# BusinessCard_LA_8CH.net
KiCad netlist of a schematic drawn in EAGLE
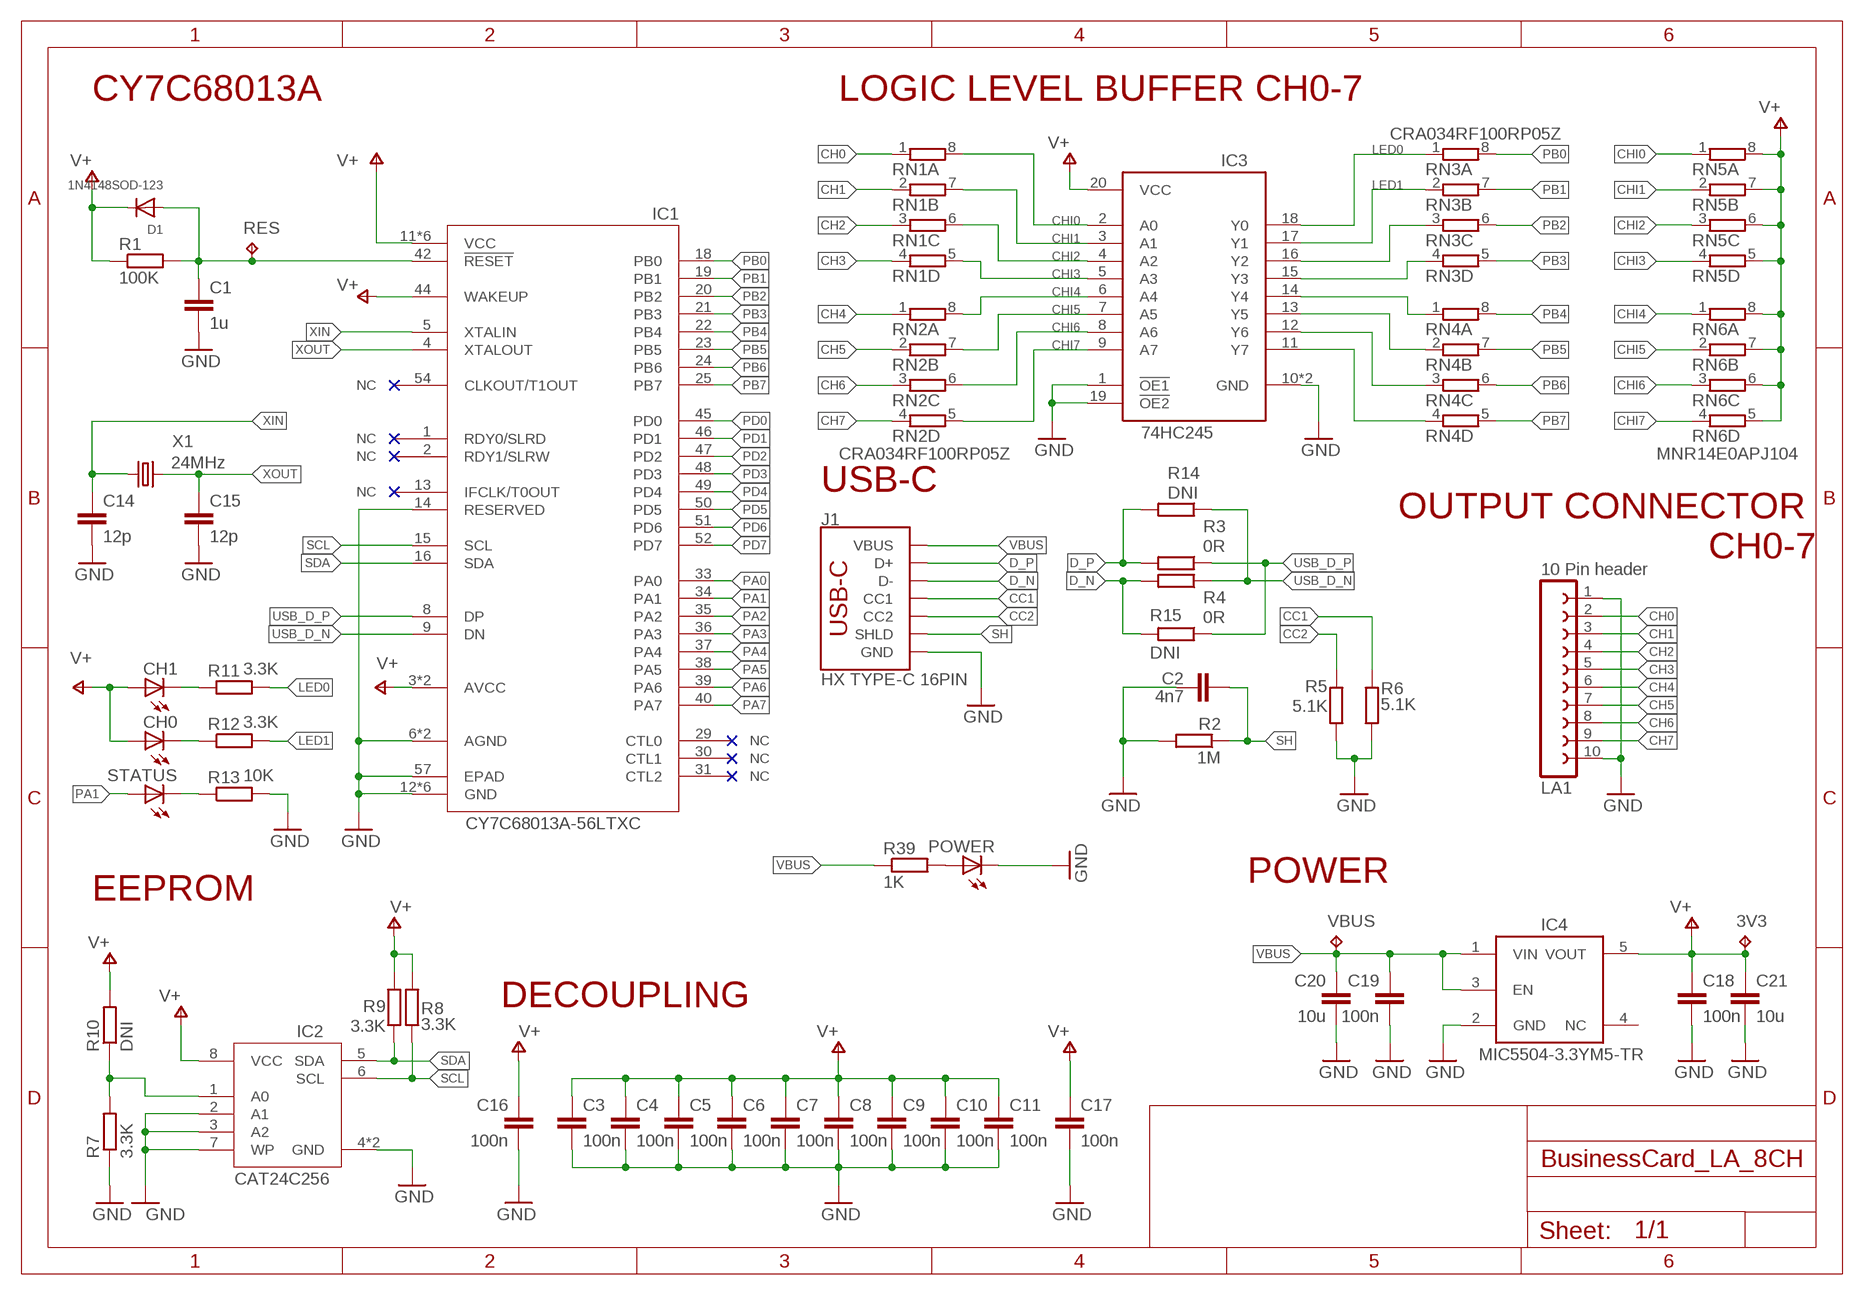
[diagram p0: schematic, sheet 1]

(export (version "E")
  (design (tool "Eeschema 10.0.6"))
  (components
    (comp (ref "3V3")
      (value "TPB1,27")
      (footprint "eagle-import:B1,27")
      (libsource (lib "eagle-import") (part "TPB1,27"))
    )
    (comp (ref "C1")
      (value "1u")
      (footprint "eagle-import:C0402K")
      (libsource (lib "eagle-import") (part "C-EUC0402K"))
    )
    (comp (ref "C2")
      (value "4n7")
      (footprint "eagle-import:C0402K")
      (libsource (lib "eagle-import") (part "C-EUC0402K"))
    )
    (comp (ref "C3")
      (value "100n")
      (footprint "eagle-import:C0402K")
      (libsource (lib "eagle-import") (part "C-EUC0402K"))
    )
    (comp (ref "C4")
      (value "100n")
      (footprint "eagle-import:C0402K")
      (libsource (lib "eagle-import") (part "C-EUC0402K"))
    )
    (comp (ref "C5")
      (value "100n")
      (footprint "eagle-import:C0402K")
      (libsource (lib "eagle-import") (part "C-EUC0402K"))
    )
    (comp (ref "C6")
      (value "100n")
      (footprint "eagle-import:C0402K")
      (libsource (lib "eagle-import") (part "C-EUC0402K"))
    )
    (comp (ref "C7")
      (value "100n")
      (footprint "eagle-import:C0402K")
      (libsource (lib "eagle-import") (part "C-EUC0402K"))
    )
    (comp (ref "C8")
      (value "100n")
      (footprint "eagle-import:C0402K")
      (libsource (lib "eagle-import") (part "C-EUC0402K"))
    )
    (comp (ref "C9")
      (value "100n")
      (footprint "eagle-import:C0402K")
      (libsource (lib "eagle-import") (part "C-EUC0402K"))
    )
    (comp (ref "C10")
      (value "100n")
      (footprint "eagle-import:C0402K")
      (libsource (lib "eagle-import") (part "C-EUC0402K"))
    )
    (comp (ref "C11")
      (value "100n")
      (footprint "eagle-import:C0402K")
      (libsource (lib "eagle-import") (part "C-EUC0402K"))
    )
    (comp (ref "C14")
      (value "12p")
      (footprint "eagle-import:C0402K")
      (libsource (lib "eagle-import") (part "C-EUC0402K"))
    )
    (comp (ref "C15")
      (value "12p")
      (footprint "eagle-import:C0402K")
      (libsource (lib "eagle-import") (part "C-EUC0402K"))
    )
    (comp (ref "C16")
      (value "100n")
      (footprint "eagle-import:C0402K")
      (libsource (lib "eagle-import") (part "C-EUC0402K"))
    )
    (comp (ref "C17")
      (value "100n")
      (footprint "eagle-import:C0402K")
      (libsource (lib "eagle-import") (part "C-EUC0402K"))
    )
    (comp (ref "C18")
      (value "100n")
      (footprint "eagle-import:C0402K")
      (libsource (lib "eagle-import") (part "C-EUC0402K"))
    )
    (comp (ref "C19")
      (value "100n")
      (footprint "eagle-import:C0402K")
      (libsource (lib "eagle-import") (part "C-EUC0402K"))
    )
    (comp (ref "C20")
      (value "10u")
      (footprint "eagle-import:C0805K")
      (libsource (lib "eagle-import") (part "C-EUC0805K"))
    )
    (comp (ref "C21")
      (value "10u")
      (footprint "eagle-import:C0805K")
      (libsource (lib "eagle-import") (part "C-EUC0805K"))
    )
    (comp (ref "CH0")
      (value "19-217/GHC-YR1S2/3T")
      (footprint "eagle-import:CHIP-LED0603")
      (libsource (lib "eagle-import") (part "LEDCHIP-LED0603"))
    )
    (comp (ref "CH1")
      (value "19-217/GHC-YR1S2/3T")
      (footprint "eagle-import:CHIP-LED0603")
      (libsource (lib "eagle-import") (part "LEDCHIP-LED0603"))
    )
    (comp (ref "D1")
      (value "1N4148SOD-123")
      (footprint "eagle-import:SOD-123FL")
      (libsource (lib "eagle-import") (part "DIODE_SOD-123FL"))
    )
    (comp (ref "IC1")
      (value "CY7C68013A-56LTXC")
      (footprint "eagle-import:QFN50P800X800X100-57T665")
      (libsource (lib "eagle-import") (part "CY7C68013A-56QFNLFXC"))
    )
    (comp (ref "IC2")
      (value "CAT24C256HU4IGT3")
      (footprint "eagle-import:SON50P300X200X50-9T130X140N")
      (libsource (lib "eagle-import") (part "CAT24C256-HU4"))
    )
    (comp (ref "IC3")
      (value "SN74LVC541ARGYR")
      (footprint "eagle-import:QFN50P350X450X100-25T305X205N")
      (libsource (lib "eagle-import") (part "74LVC541A"))
    )
    (comp (ref "IC4")
      (value "MIC5504-3.3YM5-TR")
      (footprint "eagle-import:SOT23-5")
      (libsource (lib "eagle-import") (part "MIC5504-3.3YM5-TR"))
    )
    (comp (ref "J1")
      (value "HX TYPE-C 16PIN")
      (footprint "eagle-import:USB-C-16P-2LAYER-PADS")
      (libsource (lib "eagle-import") (part "USB_C_2-LAYER_PADS"))
    )
    (comp (ref "LA1")
      (value "10 Pin header")
      (footprint "eagle-import:FE10")
      (libsource (lib "eagle-import") (part "FE10-1"))
    )
    (comp (ref "POWER")
      (value "19-213/Y2C-CQ2R2L/3T(CY)")
      (footprint "eagle-import:CHIP-LED0603")
      (libsource (lib "eagle-import") (part "LEDCHIP-LED0603"))
    )
    (comp (ref "R1")
      (value "100K")
      (footprint "eagle-import:R0402")
      (libsource (lib "eagle-import") (part "R-EU_R0402"))
    )
    (comp (ref "R2")
      (value "1M")
      (footprint "eagle-import:R0402")
      (libsource (lib "eagle-import") (part "R-EU_R0402"))
    )
    (comp (ref "R3")
      (value "0R")
      (footprint "eagle-import:R0402")
      (libsource (lib "eagle-import") (part "R-EU_R0402"))
    )
    (comp (ref "R4")
      (value "0R")
      (footprint "eagle-import:R0402")
      (libsource (lib "eagle-import") (part "R-EU_R0402"))
    )
    (comp (ref "R5")
      (value "5.1K")
      (footprint "eagle-import:R0402")
      (libsource (lib "eagle-import") (part "R-EU_R0402"))
    )
    (comp (ref "R6")
      (value "5.1K")
      (footprint "eagle-import:R0402")
      (libsource (lib "eagle-import") (part "R-EU_R0402"))
    )
    (comp (ref "R7")
      (value "3.3K")
      (footprint "eagle-import:R0402")
      (libsource (lib "eagle-import") (part "R-EU_R0402"))
    )
    (comp (ref "R8")
      (value "3.3K")
      (footprint "eagle-import:R0402")
      (libsource (lib "eagle-import") (part "R-EU_R0402"))
    )
    (comp (ref "R9")
      (value "3.3K")
      (footprint "eagle-import:R0402")
      (libsource (lib "eagle-import") (part "R-EU_R0402"))
    )
    (comp (ref "R10")
      (value "DNI")
      (footprint "eagle-import:R0402")
      (libsource (lib "eagle-import") (part "R-EU_R0402"))
    )
    (comp (ref "R11")
      (value "3.3K")
      (footprint "eagle-import:R0402")
      (libsource (lib "eagle-import") (part "R-EU_R0402"))
    )
    (comp (ref "R12")
      (value "3.3K")
      (footprint "eagle-import:R0402")
      (libsource (lib "eagle-import") (part "R-EU_R0402"))
    )
    (comp (ref "R13")
      (value "10K")
      (footprint "eagle-import:R0402")
      (libsource (lib "eagle-import") (part "R-EU_R0402"))
    )
    (comp (ref "R14")
      (value "DNI")
      (footprint "eagle-import:R0402")
      (libsource (lib "eagle-import") (part "R-EU_R0402"))
    )
    (comp (ref "R15")
      (value "DNI")
      (footprint "eagle-import:R0402")
      (libsource (lib "eagle-import") (part "R-EU_R0402"))
    )
    (comp (ref "R39")
      (value "1K")
      (footprint "eagle-import:R0402")
      (libsource (lib "eagle-import") (part "R-EU_R0402"))
    )
    (comp (ref "RES")
      (value "TPB1,27")
      (footprint "eagle-import:B1,27")
      (libsource (lib "eagle-import") (part "TPB1,27"))
    )
    (comp (ref "RN1")
      (value "CRA034RF100RP05Z")
      (footprint "eagle-import:CAT16")
      (libsource (lib "eagle-import") (part "4R-NCAT16"))
    )
    (comp (ref "RN2")
      (value "CRA034RF100RP05Z")
      (footprint "eagle-import:CAT16")
      (libsource (lib "eagle-import") (part "4R-NCAT16"))
    )
    (comp (ref "RN3")
      (value "CRA034RF100RP05Z")
      (footprint "eagle-import:CAT16")
      (libsource (lib "eagle-import") (part "4R-NCAT16"))
    )
    (comp (ref "RN4")
      (value "CRA034RF100RP05Z")
      (footprint "eagle-import:CAT16")
      (libsource (lib "eagle-import") (part "4R-NCAT16"))
    )
    (comp (ref "RN5")
      (value "MNR14E0APJ104")
      (footprint "eagle-import:CAT16")
      (libsource (lib "eagle-import") (part "4R-NCAT16"))
    )
    (comp (ref "RN6")
      (value "MNR14E0APJ104")
      (footprint "eagle-import:CAT16")
      (libsource (lib "eagle-import") (part "4R-NCAT16"))
    )
    (comp (ref "STATUS")
      (value "YLED0603B")
      (footprint "eagle-import:CHIP-LED0603")
      (libsource (lib "eagle-import") (part "LEDCHIP-LED0603"))
    )
    (comp (ref "VBUS")
      (value "TPB1,27")
      (footprint "eagle-import:B1,27")
      (libsource (lib "eagle-import") (part "TPB1,27"))
    )
    (comp (ref "X1")
      (value "24MHz")
      (footprint "eagle-import:3.2X2.5_KX-7")
      (libsource (lib "eagle-import") (part "KX-7"))
    )
  )
  (nets
    (net (code "1") (name "CC1") (class "Default")
      (node (ref "J1") (pin "A5") (pinfunction "CC1_A5") (pintype "bidirectional"))
      (node (ref "R6") (pin "1") (pinfunction "1_1") (pintype "passive"))
    )
    (net (code "2") (name "CC2") (class "Default")
      (node (ref "J1") (pin "B5") (pinfunction "CC2_B5") (pintype "bidirectional"))
      (node (ref "R5") (pin "1") (pinfunction "1_1") (pintype "passive"))
    )
    (net (code "3") (name "CH0") (class "Default")
      (node (ref "LA1") (pin "2") (pinfunction "2_2") (pintype "passive"))
      (node (ref "RN1") (pin "1") (pinfunction "1_1") (pintype "passive"))
    )
    (net (code "4") (name "CH1") (class "Default")
      (node (ref "LA1") (pin "3") (pinfunction "3_3") (pintype "passive"))
      (node (ref "RN1") (pin "2") (pinfunction "1_2") (pintype "passive"))
    )
    (net (code "5") (name "CH2") (class "Default")
      (node (ref "LA1") (pin "4") (pinfunction "4_4") (pintype "passive"))
      (node (ref "RN1") (pin "3") (pinfunction "1_3") (pintype "passive"))
    )
    (net (code "6") (name "CH3") (class "Default")
      (node (ref "LA1") (pin "5") (pinfunction "5_5") (pintype "passive"))
      (node (ref "RN1") (pin "4") (pinfunction "1_4") (pintype "passive"))
    )
    (net (code "7") (name "CH4") (class "Default")
      (node (ref "LA1") (pin "6") (pinfunction "6_6") (pintype "passive"))
      (node (ref "RN2") (pin "1") (pinfunction "1_1") (pintype "passive"))
    )
    (net (code "8") (name "CH5") (class "Default")
      (node (ref "LA1") (pin "7") (pinfunction "7_7") (pintype "passive"))
      (node (ref "RN2") (pin "2") (pinfunction "1_2") (pintype "passive"))
    )
    (net (code "9") (name "CH6") (class "Default")
      (node (ref "LA1") (pin "8") (pinfunction "8_8") (pintype "passive"))
      (node (ref "RN2") (pin "3") (pinfunction "1_3") (pintype "passive"))
    )
    (net (code "10") (name "CH7") (class "Default")
      (node (ref "LA1") (pin "9") (pinfunction "9_9") (pintype "passive"))
      (node (ref "RN2") (pin "4") (pinfunction "1_4") (pintype "passive"))
    )
    (net (code "11") (name "CHI0") (class "Default")
      (node (ref "IC3") (pin "2") (pinfunction "A0_2") (pintype "bidirectional"))
      (node (ref "RN1") (pin "8") (pinfunction "2_8") (pintype "passive"))
      (node (ref "RN5") (pin "1") (pinfunction "1_1") (pintype "passive"))
    )
    (net (code "12") (name "CHI1") (class "Default")
      (node (ref "IC3") (pin "3") (pinfunction "A1_3") (pintype "bidirectional"))
      (node (ref "RN1") (pin "7") (pinfunction "2_7") (pintype "passive"))
      (node (ref "RN5") (pin "2") (pinfunction "1_2") (pintype "passive"))
    )
    (net (code "13") (name "CHI2") (class "Default")
      (node (ref "IC3") (pin "4") (pinfunction "A2_4") (pintype "bidirectional"))
      (node (ref "RN1") (pin "6") (pinfunction "2_6") (pintype "passive"))
      (node (ref "RN5") (pin "3") (pinfunction "1_3") (pintype "passive"))
    )
    (net (code "14") (name "CHI3") (class "Default")
      (node (ref "IC3") (pin "5") (pinfunction "A3_5") (pintype "bidirectional"))
      (node (ref "RN1") (pin "5") (pinfunction "2_5") (pintype "passive"))
      (node (ref "RN5") (pin "4") (pinfunction "1_4") (pintype "passive"))
    )
    (net (code "15") (name "CHI4") (class "Default")
      (node (ref "IC3") (pin "6") (pinfunction "A4_6") (pintype "bidirectional"))
      (node (ref "RN2") (pin "8") (pinfunction "2_8") (pintype "passive"))
      (node (ref "RN6") (pin "1") (pinfunction "1_1") (pintype "passive"))
    )
    (net (code "16") (name "CHI5") (class "Default")
      (node (ref "IC3") (pin "7") (pinfunction "A5_7") (pintype "bidirectional"))
      (node (ref "RN2") (pin "7") (pinfunction "2_7") (pintype "passive"))
      (node (ref "RN6") (pin "2") (pinfunction "1_2") (pintype "passive"))
    )
    (net (code "17") (name "CHI6") (class "Default")
      (node (ref "IC3") (pin "8") (pinfunction "A6_8") (pintype "bidirectional"))
      (node (ref "RN2") (pin "6") (pinfunction "2_6") (pintype "passive"))
      (node (ref "RN6") (pin "3") (pinfunction "1_3") (pintype "passive"))
    )
    (net (code "18") (name "CHI7") (class "Default")
      (node (ref "IC3") (pin "9") (pinfunction "A7_9") (pintype "bidirectional"))
      (node (ref "RN2") (pin "5") (pinfunction "2_5") (pintype "passive"))
      (node (ref "RN6") (pin "4") (pinfunction "1_4") (pintype "passive"))
    )
    (net (code "19") (name "D_N") (class "Default")
      (node (ref "J1") (pin "A7") (pinfunction "D-_A7") (pintype "bidirectional"))
      (node (ref "J1") (pin "B7") (pinfunction "D-_B7") (pintype "bidirectional"))
      (node (ref "R15") (pin "2") (pinfunction "2_2") (pintype "passive"))
      (node (ref "R4") (pin "2") (pinfunction "2_2") (pintype "passive"))
    )
    (net (code "20") (name "D_P") (class "Default")
      (node (ref "J1") (pin "A6") (pinfunction "D+_A6") (pintype "bidirectional"))
      (node (ref "J1") (pin "B6") (pinfunction "D+_B6") (pintype "bidirectional"))
      (node (ref "R14") (pin "2") (pinfunction "2_2") (pintype "passive"))
      (node (ref "R3") (pin "2") (pinfunction "2_2") (pintype "passive"))
    )
    (net (code "21") (name "GND") (class "Default")
      (node (ref "C1") (pin "2") (pinfunction "2_2") (pintype "passive"))
      (node (ref "C10") (pin "2") (pinfunction "2_2") (pintype "passive"))
      (node (ref "C11") (pin "2") (pinfunction "2_2") (pintype "passive"))
      (node (ref "C14") (pin "2") (pinfunction "2_2") (pintype "passive"))
      (node (ref "C15") (pin "2") (pinfunction "2_2") (pintype "passive"))
      (node (ref "C16") (pin "2") (pinfunction "2_2") (pintype "passive"))
      (node (ref "C17") (pin "2") (pinfunction "2_2") (pintype "passive"))
      (node (ref "C18") (pin "2") (pinfunction "2_2") (pintype "passive"))
      (node (ref "C19") (pin "2") (pinfunction "2_2") (pintype "passive"))
      (node (ref "C2") (pin "2") (pinfunction "2_2") (pintype "passive"))
      (node (ref "C20") (pin "2") (pinfunction "2_2") (pintype "passive"))
      (node (ref "C21") (pin "2") (pinfunction "2_2") (pintype "passive"))
      (node (ref "C3") (pin "2") (pinfunction "2_2") (pintype "passive"))
      (node (ref "C4") (pin "2") (pinfunction "2_2") (pintype "passive"))
      (node (ref "C5") (pin "2") (pinfunction "2_2") (pintype "passive"))
      (node (ref "C6") (pin "2") (pinfunction "2_2") (pintype "passive"))
      (node (ref "C7") (pin "2") (pinfunction "2_2") (pintype "passive"))
      (node (ref "C8") (pin "2") (pinfunction "2_2") (pintype "passive"))
      (node (ref "C9") (pin "2") (pinfunction "2_2") (pintype "passive"))
      (node (ref "IC1") (pin "10") (pinfunction "AGND_10") (pintype "power_in"))
      (node (ref "IC1") (pin "12") (pinfunction "GND_12") (pintype "power_in"))
      (node (ref "IC1") (pin "14") (pinfunction "RESERVED_14") (pintype "bidirectional"))
      (node (ref "IC1") (pin "26") (pinfunction "GND_26") (pintype "power_in"))
      (node (ref "IC1") (pin "28") (pinfunction "GND_28") (pintype "power_in"))
      (node (ref "IC1") (pin "41") (pinfunction "GND_41") (pintype "power_in"))
      (node (ref "IC1") (pin "53") (pinfunction "GND_53") (pintype "power_in"))
      (node (ref "IC1") (pin "56") (pinfunction "GND_56") (pintype "power_in"))
      (node (ref "IC1") (pin "57") (pinfunction "EPAD_57") (pintype "power_in"))
      (node (ref "IC1") (pin "6") (pinfunction "AGND_6") (pintype "power_in"))
      (node (ref "IC2") (pin "2") (pinfunction "A1_2") (pintype "bidirectional"))
      (node (ref "IC2") (pin "3") (pinfunction "A2_3") (pintype "bidirectional"))
      (node (ref "IC2") (pin "4") (pinfunction "GND_4") (pintype "power_in"))
      (node (ref "IC2") (pin "7") (pinfunction "WP_7") (pintype "bidirectional"))
      (node (ref "IC2") (pin "9") (pinfunction "GND_9") (pintype "power_in"))
      (node (ref "IC3") (pin "1") (pinfunction "~{OE1}_1") (pintype "input"))
      (node (ref "IC3") (pin "10") (pinfunction "GND_10") (pintype "power_in"))
      (node (ref "IC3") (pin "19") (pinfunction "~{OE2}_19") (pintype "input"))
      (node (ref "IC3") (pin "PAD") (pinfunction "GND_PAD") (pintype "power_in"))
      (node (ref "IC4") (pin "2") (pinfunction "GND_2") (pintype "bidirectional"))
      (node (ref "J1") (pin "GND") (pinfunction "GND_GND") (pintype "bidirectional"))
      (node (ref "J1") (pin "GND2") (pinfunction "GND_GND2") (pintype "bidirectional"))
      (node (ref "LA1") (pin "1") (pinfunction "1_1") (pintype "passive"))
      (node (ref "LA1") (pin "10") (pinfunction "10_10") (pintype "passive"))
      (node (ref "POWER") (pin "C") (pinfunction "C_C") (pintype "passive"))
      (node (ref "R13") (pin "2") (pinfunction "2_2") (pintype "passive"))
      (node (ref "R2") (pin "2") (pinfunction "2_2") (pintype "passive"))
      (node (ref "R5") (pin "2") (pinfunction "2_2") (pintype "passive"))
      (node (ref "R6") (pin "2") (pinfunction "2_2") (pintype "passive"))
      (node (ref "R7") (pin "1") (pinfunction "1_1") (pintype "passive"))
    )
    (net (code "22") (name "LED0") (class "Default")
      (node (ref "IC3") (pin "18") (pinfunction "Y0_18") (pintype "bidirectional"))
      (node (ref "R11") (pin "2") (pinfunction "2_2") (pintype "passive"))
      (node (ref "RN3") (pin "1") (pinfunction "1_1") (pintype "passive"))
    )
    (net (code "23") (name "LED1") (class "Default")
      (node (ref "IC3") (pin "17") (pinfunction "Y1_17") (pintype "bidirectional"))
      (node (ref "R12") (pin "2") (pinfunction "2_2") (pintype "passive"))
      (node (ref "RN3") (pin "2") (pinfunction "1_2") (pintype "passive"))
    )
    (net (code "24") (name "Net-(CH0-PadC)") (class "Default")
      (node (ref "CH0") (pin "C") (pinfunction "C_C") (pintype "passive"))
      (node (ref "R12") (pin "1") (pinfunction "1_1") (pintype "passive"))
    )
    (net (code "25") (name "Net-(CH1-PadC)") (class "Default")
      (node (ref "CH1") (pin "C") (pinfunction "C_C") (pintype "passive"))
      (node (ref "R11") (pin "1") (pinfunction "1_1") (pintype "passive"))
    )
    (net (code "26") (name "Net-(IC1-~{RESET})") (class "Default")
      (node (ref "C1") (pin "1") (pinfunction "1_1") (pintype "passive"))
      (node (ref "D1") (pin "A") (pinfunction "A_A") (pintype "passive"))
      (node (ref "IC1") (pin "42") (pinfunction "~{RESET}_42") (pintype "input"))
      (node (ref "R1") (pin "2") (pinfunction "2_2") (pintype "passive"))
      (node (ref "RES") (pin "TP") (pinfunction "TP_TP") (pintype "input"))
    )
    (net (code "27") (name "Net-(IC2-A0)") (class "Default")
      (node (ref "IC2") (pin "1") (pinfunction "A0_1") (pintype "bidirectional"))
      (node (ref "R10") (pin "1") (pinfunction "1_1") (pintype "passive"))
      (node (ref "R7") (pin "2") (pinfunction "2_2") (pintype "passive"))
    )
    (net (code "28") (name "Net-(IC3-Y2)") (class "Default")
      (node (ref "IC3") (pin "16") (pinfunction "Y2_16") (pintype "bidirectional"))
      (node (ref "RN3") (pin "3") (pinfunction "1_3") (pintype "passive"))
    )
    (net (code "29") (name "Net-(IC3-Y3)") (class "Default")
      (node (ref "IC3") (pin "15") (pinfunction "Y3_15") (pintype "bidirectional"))
      (node (ref "RN3") (pin "4") (pinfunction "1_4") (pintype "passive"))
    )
    (net (code "30") (name "Net-(IC3-Y4)") (class "Default")
      (node (ref "IC3") (pin "14") (pinfunction "Y4_14") (pintype "bidirectional"))
      (node (ref "RN4") (pin "1") (pinfunction "1_1") (pintype "passive"))
    )
    (net (code "31") (name "Net-(IC3-Y5)") (class "Default")
      (node (ref "IC3") (pin "13") (pinfunction "Y5_13") (pintype "bidirectional"))
      (node (ref "RN4") (pin "2") (pinfunction "1_2") (pintype "passive"))
    )
    (net (code "32") (name "Net-(IC3-Y6)") (class "Default")
      (node (ref "IC3") (pin "12") (pinfunction "Y6_12") (pintype "bidirectional"))
      (node (ref "RN4") (pin "3") (pinfunction "1_3") (pintype "passive"))
    )
    (net (code "33") (name "Net-(IC3-Y7)") (class "Default")
      (node (ref "IC3") (pin "11") (pinfunction "Y7_11") (pintype "bidirectional"))
      (node (ref "RN4") (pin "4") (pinfunction "1_4") (pintype "passive"))
    )
    (net (code "34") (name "Net-(POWER-PadA)") (class "Default")
      (node (ref "POWER") (pin "A") (pinfunction "A_A") (pintype "passive"))
      (node (ref "R39") (pin "2") (pinfunction "2_2") (pintype "passive"))
    )
    (net (code "35") (name "Net-(R13-Pad1)") (class "Default")
      (node (ref "R13") (pin "1") (pinfunction "1_1") (pintype "passive"))
      (node (ref "STATUS") (pin "C") (pinfunction "C_C") (pintype "passive"))
    )
    (net (code "36") (name "PA0") (class "Default")
      (node (ref "IC1") (pin "33") (pinfunction "PA0_33") (pintype "bidirectional"))
    )
    (net (code "37") (name "PA1") (class "Default")
      (node (ref "IC1") (pin "34") (pinfunction "PA1_34") (pintype "bidirectional"))
      (node (ref "STATUS") (pin "A") (pinfunction "A_A") (pintype "passive"))
    )
    (net (code "38") (name "PA2") (class "Default")
      (node (ref "IC1") (pin "35") (pinfunction "PA2_35") (pintype "bidirectional"))
    )
    (net (code "39") (name "PA3") (class "Default")
      (node (ref "IC1") (pin "36") (pinfunction "PA3_36") (pintype "bidirectional"))
    )
    (net (code "40") (name "PA4") (class "Default")
      (node (ref "IC1") (pin "37") (pinfunction "PA4_37") (pintype "bidirectional"))
    )
    (net (code "41") (name "PA5") (class "Default")
      (node (ref "IC1") (pin "38") (pinfunction "PA5_38") (pintype "bidirectional"))
    )
    (net (code "42") (name "PA6") (class "Default")
      (node (ref "IC1") (pin "39") (pinfunction "PA6_39") (pintype "bidirectional"))
    )
    (net (code "43") (name "PA7") (class "Default")
      (node (ref "IC1") (pin "40") (pinfunction "PA7_40") (pintype "bidirectional"))
    )
    (net (code "44") (name "PB0") (class "Default")
      (node (ref "IC1") (pin "18") (pinfunction "PB0_18") (pintype "bidirectional"))
      (node (ref "RN3") (pin "8") (pinfunction "2_8") (pintype "passive"))
    )
    (net (code "45") (name "PB1") (class "Default")
      (node (ref "IC1") (pin "19") (pinfunction "PB1_19") (pintype "bidirectional"))
      (node (ref "RN3") (pin "7") (pinfunction "2_7") (pintype "passive"))
    )
    (net (code "46") (name "PB2") (class "Default")
      (node (ref "IC1") (pin "20") (pinfunction "PB2_20") (pintype "bidirectional"))
      (node (ref "RN3") (pin "6") (pinfunction "2_6") (pintype "passive"))
    )
    (net (code "47") (name "PB3") (class "Default")
      (node (ref "IC1") (pin "21") (pinfunction "PB3_21") (pintype "bidirectional"))
      (node (ref "RN3") (pin "5") (pinfunction "2_5") (pintype "passive"))
    )
    (net (code "48") (name "PB4") (class "Default")
      (node (ref "IC1") (pin "22") (pinfunction "PB4_22") (pintype "bidirectional"))
      (node (ref "RN4") (pin "8") (pinfunction "2_8") (pintype "passive"))
    )
    (net (code "49") (name "PB5") (class "Default")
      (node (ref "IC1") (pin "23") (pinfunction "PB5_23") (pintype "bidirectional"))
      (node (ref "RN4") (pin "7") (pinfunction "2_7") (pintype "passive"))
    )
    (net (code "50") (name "PB6") (class "Default")
      (node (ref "IC1") (pin "24") (pinfunction "PB6_24") (pintype "bidirectional"))
      (node (ref "RN4") (pin "6") (pinfunction "2_6") (pintype "passive"))
    )
    (net (code "51") (name "PB7") (class "Default")
      (node (ref "IC1") (pin "25") (pinfunction "PB7_25") (pintype "bidirectional"))
      (node (ref "RN4") (pin "5") (pinfunction "2_5") (pintype "passive"))
    )
    (net (code "52") (name "PD0") (class "Default")
      (node (ref "IC1") (pin "45") (pinfunction "PD0_45") (pintype "bidirectional"))
    )
    (net (code "53") (name "PD1") (class "Default")
      (node (ref "IC1") (pin "46") (pinfunction "PD1_46") (pintype "bidirectional"))
    )
    (net (code "54") (name "PD2") (class "Default")
      (node (ref "IC1") (pin "47") (pinfunction "PD2_47") (pintype "bidirectional"))
    )
    (net (code "55") (name "PD3") (class "Default")
      (node (ref "IC1") (pin "48") (pinfunction "PD3_48") (pintype "bidirectional"))
    )
    (net (code "56") (name "PD4") (class "Default")
      (node (ref "IC1") (pin "49") (pinfunction "PD4_49") (pintype "bidirectional"))
    )
    (net (code "57") (name "PD5") (class "Default")
      (node (ref "IC1") (pin "50") (pinfunction "PD5_50") (pintype "bidirectional"))
    )
    (net (code "58") (name "PD6") (class "Default")
      (node (ref "IC1") (pin "51") (pinfunction "PD6_51") (pintype "bidirectional"))
    )
    (net (code "59") (name "PD7") (class "Default")
      (node (ref "IC1") (pin "52") (pinfunction "PD7_52") (pintype "bidirectional"))
    )
    (net (code "60") (name "SCL") (class "Default")
      (node (ref "IC1") (pin "15") (pinfunction "SCL_15") (pintype "bidirectional"))
      (node (ref "IC2") (pin "6") (pinfunction "SCL_6") (pintype "bidirectional"))
      (node (ref "R8") (pin "1") (pinfunction "1_1") (pintype "passive"))
    )
    (net (code "61") (name "SDA") (class "Default")
      (node (ref "IC1") (pin "16") (pinfunction "SDA_16") (pintype "bidirectional"))
      (node (ref "IC2") (pin "5") (pinfunction "SDA_5") (pintype "bidirectional"))
      (node (ref "R9") (pin "1") (pinfunction "1_1") (pintype "passive"))
    )
    (net (code "62") (name "SH") (class "Default")
      (node (ref "C2") (pin "1") (pinfunction "1_1") (pintype "passive"))
      (node (ref "J1") (pin "SHLD1") (pinfunction "SHLD_SHLD1") (pintype "bidirectional"))
      (node (ref "J1") (pin "SHLD2") (pinfunction "SHLD_SHLD2") (pintype "bidirectional"))
      (node (ref "J1") (pin "SHLD3") (pinfunction "SHLD_SHLD3") (pintype "bidirectional"))
      (node (ref "J1") (pin "SHLD4") (pinfunction "SHLD_SHLD4") (pintype "bidirectional"))
      (node (ref "R2") (pin "1") (pinfunction "1_1") (pintype "passive"))
    )
    (net (code "63") (name "USB_D_N") (class "Default")
      (node (ref "IC1") (pin "9") (pinfunction "DN_9") (pintype "bidirectional"))
      (node (ref "R14") (pin "1") (pinfunction "1_1") (pintype "passive"))
      (node (ref "R4") (pin "1") (pinfunction "1_1") (pintype "passive"))
    )
    (net (code "64") (name "USB_D_P") (class "Default")
      (node (ref "IC1") (pin "8") (pinfunction "DP_8") (pintype "bidirectional"))
      (node (ref "R15") (pin "1") (pinfunction "1_1") (pintype "passive"))
      (node (ref "R3") (pin "1") (pinfunction "1_1") (pintype "passive"))
    )
    (net (code "65") (name "V+") (class "Default")
      (node (ref "3V3") (pin "TP") (pinfunction "TP_TP") (pintype "input"))
      (node (ref "C10") (pin "1") (pinfunction "1_1") (pintype "passive"))
      (node (ref "C11") (pin "1") (pinfunction "1_1") (pintype "passive"))
      (node (ref "C16") (pin "1") (pinfunction "1_1") (pintype "passive"))
      (node (ref "C17") (pin "1") (pinfunction "1_1") (pintype "passive"))
      (node (ref "C18") (pin "1") (pinfunction "1_1") (pintype "passive"))
      (node (ref "C21") (pin "1") (pinfunction "1_1") (pintype "passive"))
      (node (ref "C3") (pin "1") (pinfunction "1_1") (pintype "passive"))
      (node (ref "C4") (pin "1") (pinfunction "1_1") (pintype "passive"))
      (node (ref "C5") (pin "1") (pinfunction "1_1") (pintype "passive"))
      (node (ref "C6") (pin "1") (pinfunction "1_1") (pintype "passive"))
      (node (ref "C7") (pin "1") (pinfunction "1_1") (pintype "passive"))
      (node (ref "C8") (pin "1") (pinfunction "1_1") (pintype "passive"))
      (node (ref "C9") (pin "1") (pinfunction "1_1") (pintype "passive"))
      (node (ref "CH0") (pin "A") (pinfunction "A_A") (pintype "passive"))
      (node (ref "CH1") (pin "A") (pinfunction "A_A") (pintype "passive"))
      (node (ref "D1") (pin "C") (pinfunction "C_C") (pintype "passive"))
      (node (ref "IC1") (pin "11") (pinfunction "VCC_11") (pintype "power_in"))
      (node (ref "IC1") (pin "17") (pinfunction "VCC_17") (pintype "power_in"))
      (node (ref "IC1") (pin "27") (pinfunction "VCC_27") (pintype "power_in"))
      (node (ref "IC1") (pin "3") (pinfunction "AVCC_3") (pintype "power_in"))
      (node (ref "IC1") (pin "32") (pinfunction "VCC_32") (pintype "power_in"))
      (node (ref "IC1") (pin "43") (pinfunction "VCC_43") (pintype "power_in"))
      (node (ref "IC1") (pin "44") (pinfunction "WAKEUP_44") (pintype "input"))
      (node (ref "IC1") (pin "55") (pinfunction "VCC_55") (pintype "power_in"))
      (node (ref "IC1") (pin "7") (pinfunction "AVCC_7") (pintype "power_in"))
      (node (ref "IC2") (pin "8") (pinfunction "VCC_8") (pintype "power_in"))
      (node (ref "IC3") (pin "20") (pinfunction "VCC_20") (pintype "power_in"))
      (node (ref "IC4") (pin "5") (pinfunction "VOUT_5") (pintype "bidirectional"))
      (node (ref "R1") (pin "1") (pinfunction "1_1") (pintype "passive"))
      (node (ref "R10") (pin "2") (pinfunction "2_2") (pintype "passive"))
      (node (ref "R8") (pin "2") (pinfunction "2_2") (pintype "passive"))
      (node (ref "R9") (pin "2") (pinfunction "2_2") (pintype "passive"))
      (node (ref "RN5") (pin "5") (pinfunction "2_5") (pintype "passive"))
      (node (ref "RN5") (pin "6") (pinfunction "2_6") (pintype "passive"))
      (node (ref "RN5") (pin "7") (pinfunction "2_7") (pintype "passive"))
      (node (ref "RN5") (pin "8") (pinfunction "2_8") (pintype "passive"))
      (node (ref "RN6") (pin "5") (pinfunction "2_5") (pintype "passive"))
      (node (ref "RN6") (pin "6") (pinfunction "2_6") (pintype "passive"))
      (node (ref "RN6") (pin "7") (pinfunction "2_7") (pintype "passive"))
      (node (ref "RN6") (pin "8") (pinfunction "2_8") (pintype "passive"))
    )
    (net (code "66") (name "VBUS") (class "Default")
      (node (ref "C19") (pin "1") (pinfunction "1_1") (pintype "passive"))
      (node (ref "C20") (pin "1") (pinfunction "1_1") (pintype "passive"))
      (node (ref "IC4") (pin "1") (pinfunction "VIN_1") (pintype "bidirectional"))
      (node (ref "IC4") (pin "3") (pinfunction "EN_3") (pintype "bidirectional"))
      (node (ref "J1") (pin "VBUS1") (pinfunction "VBUS_VBUS1") (pintype "bidirectional"))
      (node (ref "J1") (pin "VBUS2") (pinfunction "VBUS_VBUS2") (pintype "bidirectional"))
      (node (ref "R39") (pin "1") (pinfunction "1_1") (pintype "passive"))
      (node (ref "VBUS") (pin "TP") (pinfunction "TP_TP") (pintype "input"))
    )
    (net (code "67") (name "XIN") (class "Default")
      (node (ref "C14") (pin "1") (pinfunction "1_1") (pintype "passive"))
      (node (ref "IC1") (pin "5") (pinfunction "XTALIN_5") (pintype "input"))
      (node (ref "X1") (pin "1") (pinfunction "1_1") (pintype "passive"))
    )
    (net (code "68") (name "XOUT") (class "Default")
      (node (ref "C15") (pin "1") (pinfunction "1_1") (pintype "passive"))
      (node (ref "IC1") (pin "4") (pinfunction "XTALOUT_4") (pintype "output"))
      (node (ref "X1") (pin "3") (pinfunction "2_3") (pintype "passive"))
    )
    (net (code "69") (name "unconnected-(IC1-CLKOUT{slash}T1OUT-Pad54)") (class "Default")
      (node (ref "IC1") (pin "54") (pinfunction "CLKOUT/T1OUT_54") (pintype "bidirectional"))
    )
    (net (code "70") (name "unconnected-(IC1-CTL0-Pad29)") (class "Default")
      (node (ref "IC1") (pin "29") (pinfunction "CTL0_29") (pintype "bidirectional"))
    )
    (net (code "71") (name "unconnected-(IC1-CTL1-Pad30)") (class "Default")
      (node (ref "IC1") (pin "30") (pinfunction "CTL1_30") (pintype "bidirectional"))
    )
    (net (code "72") (name "unconnected-(IC1-CTL2-Pad31)") (class "Default")
      (node (ref "IC1") (pin "31") (pinfunction "CTL2_31") (pintype "bidirectional"))
    )
    (net (code "73") (name "unconnected-(IC1-IFCLK{slash}T0OUT-Pad13)") (class "Default")
      (node (ref "IC1") (pin "13") (pinfunction "IFCLK/T0OUT_13") (pintype "bidirectional"))
    )
    (net (code "74") (name "unconnected-(IC1-RDY0{slash}SLRD-Pad1)") (class "Default")
      (node (ref "IC1") (pin "1") (pinfunction "RDY0/SLRD_1") (pintype "bidirectional"))
    )
    (net (code "75") (name "unconnected-(IC1-RDY1{slash}SLRW-Pad2)") (class "Default")
      (node (ref "IC1") (pin "2") (pinfunction "RDY1/SLRW_2") (pintype "bidirectional"))
    )
    (net (code "76") (name "unconnected-(IC4-NC-Pad4)") (class "Default")
      (node (ref "IC4") (pin "4") (pinfunction "NC_4") (pintype "bidirectional"))
    )
  )
)
